# SubSchHVCotrol.net
KiCad netlist of a schematic drawn in Altium Designer
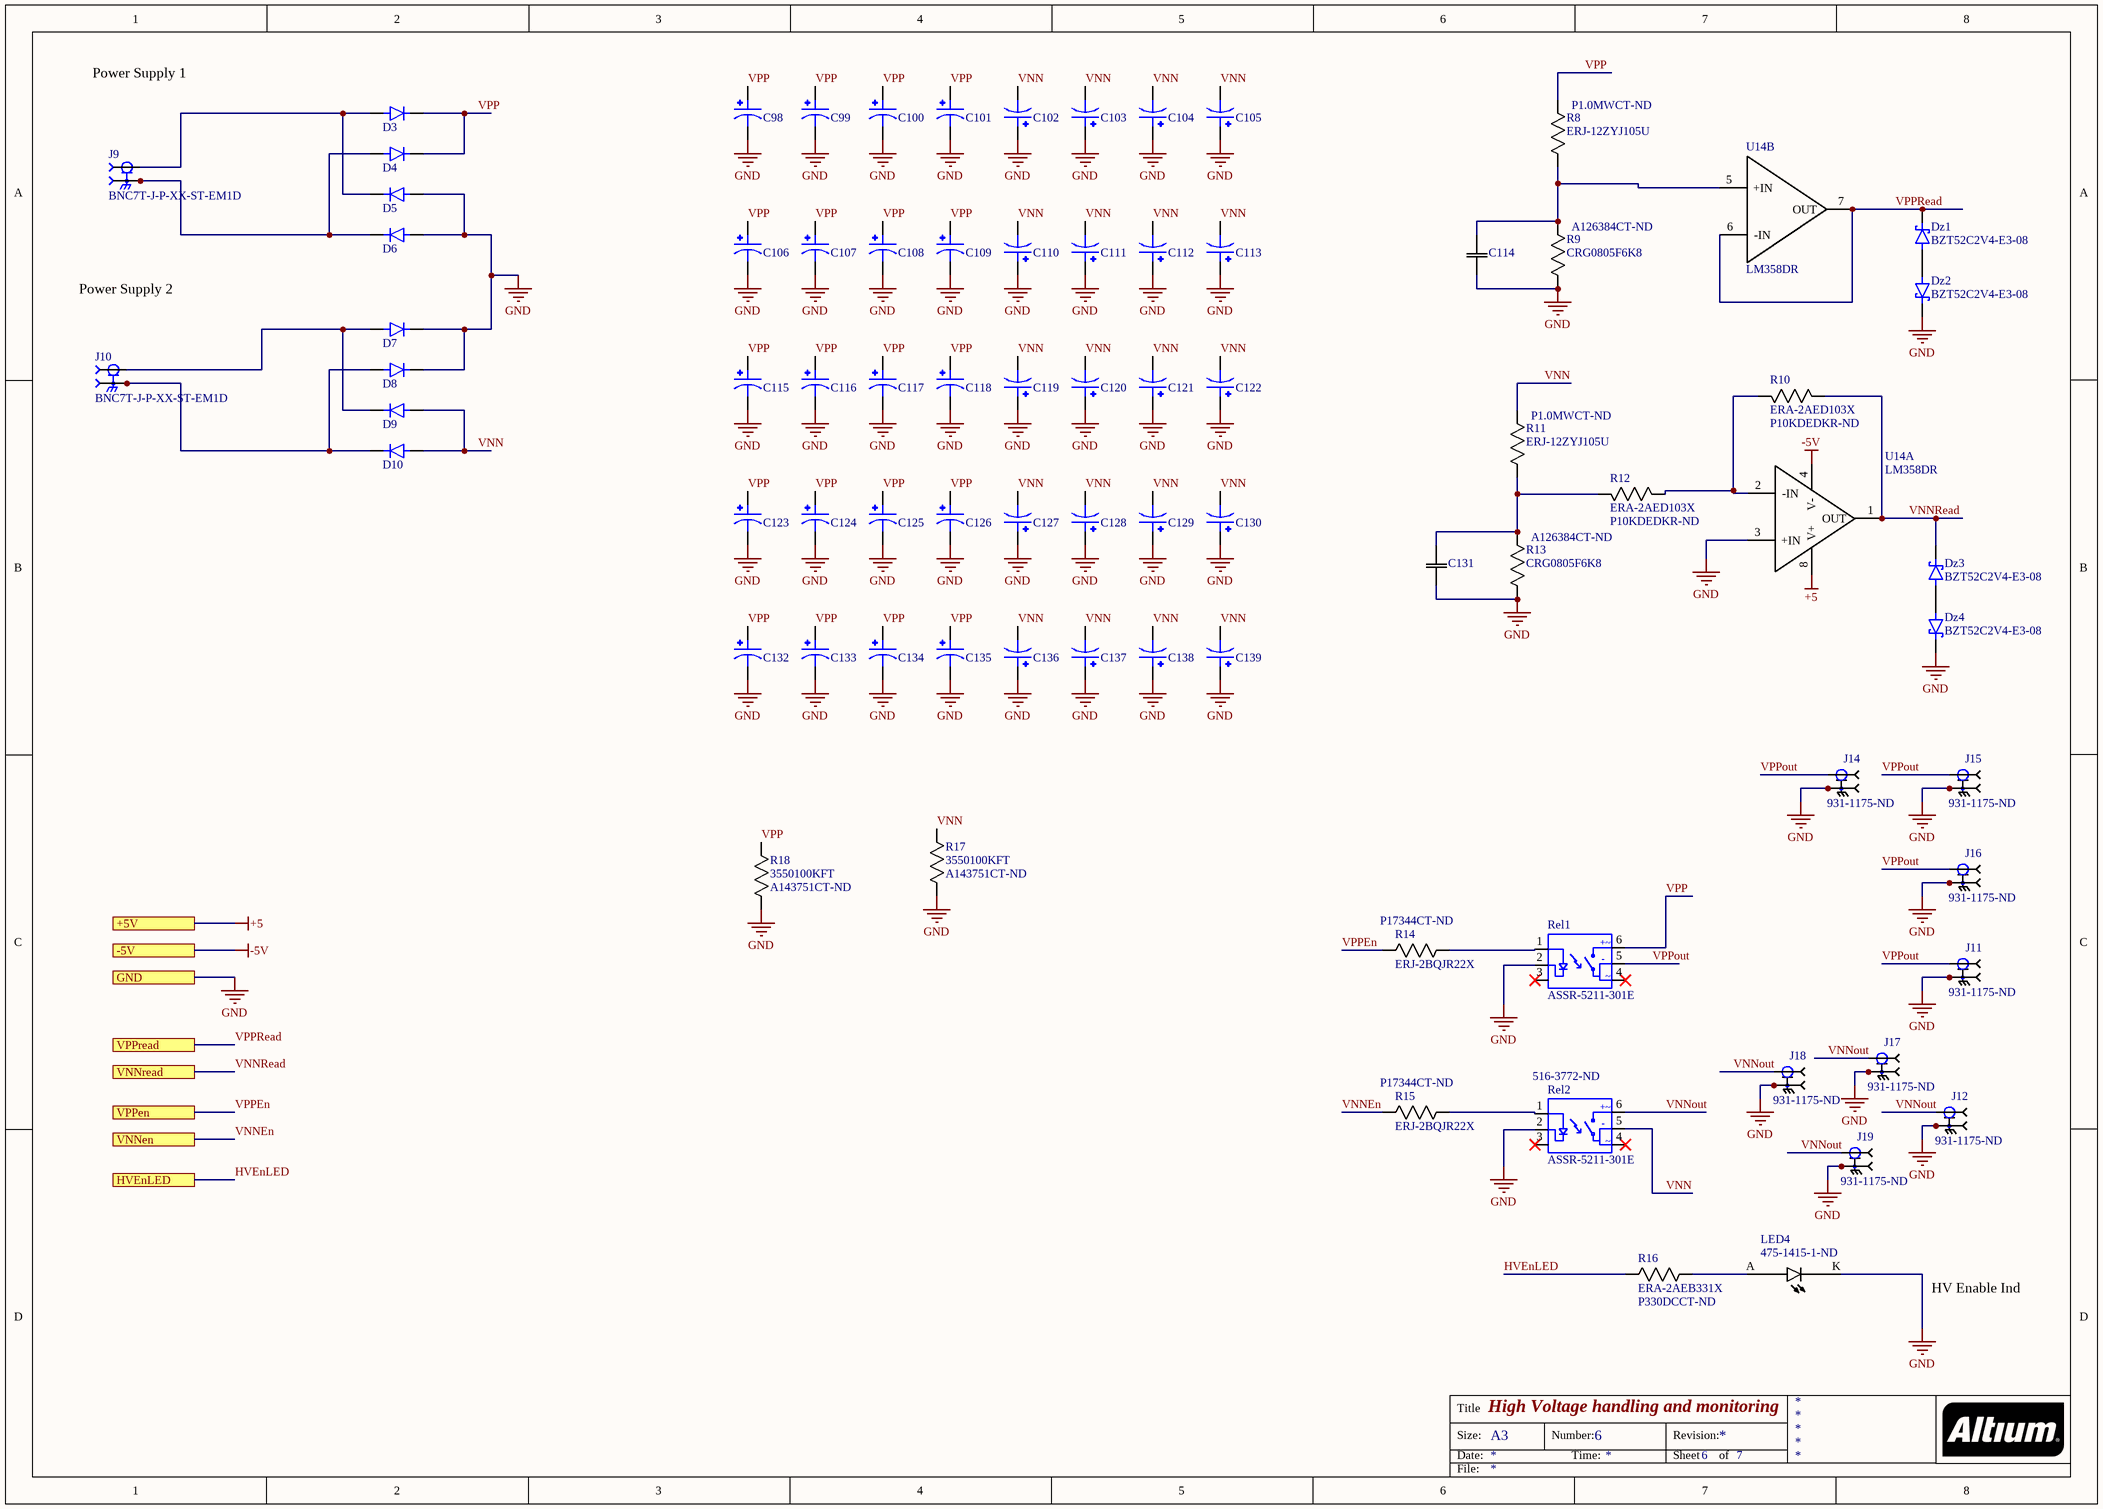
[diagram p0: SubSchHVCotrol.SchDoc]

(export (version "E")
  (design (tool "Eeschema 10.0.6"))
  (components
    (comp (ref "C98")
      (value "EDH336M400A9TAA")
      (footprint "CAPAE1700X1700N")
      (description "33ÂµF 400V Aluminum Electrolytic Capacitors Radial, Can - SMD 2000 Hrs @ 105Â°C")
      (fields (field (name "MF") "KEMET"))
      (libsource (lib "") (part "EDH336M400A9TAA_1"))
    )
    (comp (ref "C99")
      (value "EDH336M400A9TAA")
      (footprint "CAPAE1700X1700N")
      (description "33ÂµF 400V Aluminum Electrolytic Capacitors Radial, Can - SMD 2000 Hrs @ 105Â°C")
      (fields (field (name "MF") "KEMET"))
      (libsource (lib "") (part "EDH336M400A9TAA_1"))
    )
    (comp (ref "C100")
      (value "EDH336M400A9TAA")
      (footprint "CAPAE1700X1700N")
      (description "33ÂµF 400V Aluminum Electrolytic Capacitors Radial, Can - SMD 2000 Hrs @ 105Â°C")
      (fields (field (name "MF") "KEMET"))
      (libsource (lib "") (part "EDH336M400A9TAA_1"))
    )
    (comp (ref "C101")
      (value "EDH336M400A9TAA")
      (footprint "CAPAE1700X1700N")
      (description "33ÂµF 400V Aluminum Electrolytic Capacitors Radial, Can - SMD 2000 Hrs @ 105Â°C")
      (fields (field (name "MF") "KEMET"))
      (libsource (lib "") (part "EDH336M400A9TAA_1"))
    )
    (comp (ref "C102")
      (value "EDH336M400A9TAA")
      (footprint "CAPAE1700X1700N")
      (description "33ÂµF 400V Aluminum Electrolytic Capacitors Radial, Can - SMD 2000 Hrs @ 105Â°C")
      (fields (field (name "MF") "KEMET"))
      (libsource (lib "Afshin Library") (part "EDH336M400A9TAA"))
    )
    (comp (ref "C103")
      (value "EDH336M400A9TAA")
      (footprint "CAPAE1700X1700N")
      (description "33ÂµF 400V Aluminum Electrolytic Capacitors Radial, Can - SMD 2000 Hrs @ 105Â°C")
      (fields (field (name "MF") "KEMET"))
      (libsource (lib "Afshin Library") (part "EDH336M400A9TAA"))
    )
    (comp (ref "C104")
      (value "EDH336M400A9TAA")
      (footprint "CAPAE1700X1700N")
      (description "33ÂµF 400V Aluminum Electrolytic Capacitors Radial, Can - SMD 2000 Hrs @ 105Â°C")
      (fields (field (name "MF") "KEMET"))
      (libsource (lib "Afshin Library") (part "EDH336M400A9TAA"))
    )
    (comp (ref "C105")
      (value "EDH336M400A9TAA")
      (footprint "CAPAE1700X1700N")
      (description "33ÂµF 400V Aluminum Electrolytic Capacitors Radial, Can - SMD 2000 Hrs @ 105Â°C")
      (fields (field (name "MF") "KEMET"))
      (libsource (lib "Afshin Library") (part "EDH336M400A9TAA"))
    )
    (comp (ref "C106")
      (value "EDH336M400A9TAA")
      (footprint "CAPAE1700X1700N")
      (description "33ÂµF 400V Aluminum Electrolytic Capacitors Radial, Can - SMD 2000 Hrs @ 105Â°C")
      (fields (field (name "MF") "KEMET"))
      (libsource (lib "") (part "EDH336M400A9TAA_1"))
    )
    (comp (ref "C107")
      (value "EDH336M400A9TAA")
      (footprint "CAPAE1700X1700N")
      (description "33ÂµF 400V Aluminum Electrolytic Capacitors Radial, Can - SMD 2000 Hrs @ 105Â°C")
      (fields (field (name "MF") "KEMET"))
      (libsource (lib "") (part "EDH336M400A9TAA_1"))
    )
    (comp (ref "C108")
      (value "EDH336M400A9TAA")
      (footprint "CAPAE1700X1700N")
      (description "33ÂµF 400V Aluminum Electrolytic Capacitors Radial, Can - SMD 2000 Hrs @ 105Â°C")
      (fields (field (name "MF") "KEMET"))
      (libsource (lib "") (part "EDH336M400A9TAA_1"))
    )
    (comp (ref "C109")
      (value "EDH336M400A9TAA")
      (footprint "CAPAE1700X1700N")
      (description "33ÂµF 400V Aluminum Electrolytic Capacitors Radial, Can - SMD 2000 Hrs @ 105Â°C")
      (fields (field (name "MF") "KEMET"))
      (libsource (lib "") (part "EDH336M400A9TAA_1"))
    )
    (comp (ref "C110")
      (value "EDH336M400A9TAA")
      (footprint "CAPAE1700X1700N")
      (description "33ÂµF 400V Aluminum Electrolytic Capacitors Radial, Can - SMD 2000 Hrs @ 105Â°C")
      (fields (field (name "MF") "KEMET"))
      (libsource (lib "Afshin Library") (part "EDH336M400A9TAA"))
    )
    (comp (ref "C111")
      (value "EDH336M400A9TAA")
      (footprint "CAPAE1700X1700N")
      (description "33ÂµF 400V Aluminum Electrolytic Capacitors Radial, Can - SMD 2000 Hrs @ 105Â°C")
      (fields (field (name "MF") "KEMET"))
      (libsource (lib "Afshin Library") (part "EDH336M400A9TAA"))
    )
    (comp (ref "C112")
      (value "EDH336M400A9TAA")
      (footprint "CAPAE1700X1700N")
      (description "33ÂµF 400V Aluminum Electrolytic Capacitors Radial, Can - SMD 2000 Hrs @ 105Â°C")
      (fields (field (name "MF") "KEMET"))
      (libsource (lib "Afshin Library") (part "EDH336M400A9TAA"))
    )
    (comp (ref "C113")
      (value "EDH336M400A9TAA")
      (footprint "CAPAE1700X1700N")
      (description "33ÂµF 400V Aluminum Electrolytic Capacitors Radial, Can - SMD 2000 Hrs @ 105Â°C")
      (fields (field (name "MF") "KEMET"))
      (libsource (lib "Afshin Library") (part "EDH336M400A9TAA"))
    )
    (comp (ref "C114")
      (value "C0805C104Z5VACTU")
      (footprint "C0805")
      (libsource (lib "Afshin Library") (part "Cap_0805"))
    )
    (comp (ref "C115")
      (value "EDH336M400A9TAA")
      (footprint "CAPAE1700X1700N")
      (description "33ÂµF 400V Aluminum Electrolytic Capacitors Radial, Can - SMD 2000 Hrs @ 105Â°C")
      (fields (field (name "MF") "KEMET"))
      (libsource (lib "") (part "EDH336M400A9TAA_1"))
    )
    (comp (ref "C116")
      (value "EDH336M400A9TAA")
      (footprint "CAPAE1700X1700N")
      (description "33ÂµF 400V Aluminum Electrolytic Capacitors Radial, Can - SMD 2000 Hrs @ 105Â°C")
      (fields (field (name "MF") "KEMET"))
      (libsource (lib "") (part "EDH336M400A9TAA_1"))
    )
    (comp (ref "C117")
      (value "EDH336M400A9TAA")
      (footprint "CAPAE1700X1700N")
      (description "33ÂµF 400V Aluminum Electrolytic Capacitors Radial, Can - SMD 2000 Hrs @ 105Â°C")
      (fields (field (name "MF") "KEMET"))
      (libsource (lib "") (part "EDH336M400A9TAA_1"))
    )
    (comp (ref "C118")
      (value "EDH336M400A9TAA")
      (footprint "CAPAE1700X1700N")
      (description "33ÂµF 400V Aluminum Electrolytic Capacitors Radial, Can - SMD 2000 Hrs @ 105Â°C")
      (fields (field (name "MF") "KEMET"))
      (libsource (lib "") (part "EDH336M400A9TAA_1"))
    )
    (comp (ref "C119")
      (value "EDH336M400A9TAA")
      (footprint "CAPAE1700X1700N")
      (description "33ÂµF 400V Aluminum Electrolytic Capacitors Radial, Can - SMD 2000 Hrs @ 105Â°C")
      (fields (field (name "MF") "KEMET"))
      (libsource (lib "Afshin Library") (part "EDH336M400A9TAA"))
    )
    (comp (ref "C120")
      (value "EDH336M400A9TAA")
      (footprint "CAPAE1700X1700N")
      (description "33ÂµF 400V Aluminum Electrolytic Capacitors Radial, Can - SMD 2000 Hrs @ 105Â°C")
      (fields (field (name "MF") "KEMET"))
      (libsource (lib "Afshin Library") (part "EDH336M400A9TAA"))
    )
    (comp (ref "C121")
      (value "EDH336M400A9TAA")
      (footprint "CAPAE1700X1700N")
      (description "33ÂµF 400V Aluminum Electrolytic Capacitors Radial, Can - SMD 2000 Hrs @ 105Â°C")
      (fields (field (name "MF") "KEMET"))
      (libsource (lib "Afshin Library") (part "EDH336M400A9TAA"))
    )
    (comp (ref "C122")
      (value "EDH336M400A9TAA")
      (footprint "CAPAE1700X1700N")
      (description "33ÂµF 400V Aluminum Electrolytic Capacitors Radial, Can - SMD 2000 Hrs @ 105Â°C")
      (fields (field (name "MF") "KEMET"))
      (libsource (lib "Afshin Library") (part "EDH336M400A9TAA"))
    )
    (comp (ref "C123")
      (value "EDH336M400A9TAA")
      (footprint "CAPAE1700X1700N")
      (description "33ÂµF 400V Aluminum Electrolytic Capacitors Radial, Can - SMD 2000 Hrs @ 105Â°C")
      (fields (field (name "MF") "KEMET"))
      (libsource (lib "") (part "EDH336M400A9TAA_1"))
    )
    (comp (ref "C124")
      (value "EDH336M400A9TAA")
      (footprint "CAPAE1700X1700N")
      (description "33ÂµF 400V Aluminum Electrolytic Capacitors Radial, Can - SMD 2000 Hrs @ 105Â°C")
      (fields (field (name "MF") "KEMET"))
      (libsource (lib "") (part "EDH336M400A9TAA_1"))
    )
    (comp (ref "C125")
      (value "EDH336M400A9TAA")
      (footprint "CAPAE1700X1700N")
      (description "33ÂµF 400V Aluminum Electrolytic Capacitors Radial, Can - SMD 2000 Hrs @ 105Â°C")
      (fields (field (name "MF") "KEMET"))
      (libsource (lib "") (part "EDH336M400A9TAA_1"))
    )
    (comp (ref "C126")
      (value "EDH336M400A9TAA")
      (footprint "CAPAE1700X1700N")
      (description "33ÂµF 400V Aluminum Electrolytic Capacitors Radial, Can - SMD 2000 Hrs @ 105Â°C")
      (fields (field (name "MF") "KEMET"))
      (libsource (lib "") (part "EDH336M400A9TAA_1"))
    )
    (comp (ref "C127")
      (value "EDH336M400A9TAA")
      (footprint "CAPAE1700X1700N")
      (description "33ÂµF 400V Aluminum Electrolytic Capacitors Radial, Can - SMD 2000 Hrs @ 105Â°C")
      (fields (field (name "MF") "KEMET"))
      (libsource (lib "Afshin Library") (part "EDH336M400A9TAA"))
    )
    (comp (ref "C128")
      (value "EDH336M400A9TAA")
      (footprint "CAPAE1700X1700N")
      (description "33ÂµF 400V Aluminum Electrolytic Capacitors Radial, Can - SMD 2000 Hrs @ 105Â°C")
      (fields (field (name "MF") "KEMET"))
      (libsource (lib "Afshin Library") (part "EDH336M400A9TAA"))
    )
    (comp (ref "C129")
      (value "EDH336M400A9TAA")
      (footprint "CAPAE1700X1700N")
      (description "33ÂµF 400V Aluminum Electrolytic Capacitors Radial, Can - SMD 2000 Hrs @ 105Â°C")
      (fields (field (name "MF") "KEMET"))
      (libsource (lib "Afshin Library") (part "EDH336M400A9TAA"))
    )
    (comp (ref "C130")
      (value "EDH336M400A9TAA")
      (footprint "CAPAE1700X1700N")
      (description "33ÂµF 400V Aluminum Electrolytic Capacitors Radial, Can - SMD 2000 Hrs @ 105Â°C")
      (fields (field (name "MF") "KEMET"))
      (libsource (lib "Afshin Library") (part "EDH336M400A9TAA"))
    )
    (comp (ref "C131")
      (value "C0805C104Z5VACTU")
      (footprint "C0805")
      (libsource (lib "Afshin Library") (part "Cap_0805"))
    )
    (comp (ref "C132")
      (value "EDH336M400A9TAA")
      (footprint "CAPAE1700X1700N")
      (description "33ÂµF 400V Aluminum Electrolytic Capacitors Radial, Can - SMD 2000 Hrs @ 105Â°C")
      (fields (field (name "MF") "KEMET"))
      (libsource (lib "") (part "EDH336M400A9TAA_1"))
    )
    (comp (ref "C133")
      (value "EDH336M400A9TAA")
      (footprint "CAPAE1700X1700N")
      (description "33ÂµF 400V Aluminum Electrolytic Capacitors Radial, Can - SMD 2000 Hrs @ 105Â°C")
      (fields (field (name "MF") "KEMET"))
      (libsource (lib "") (part "EDH336M400A9TAA_1"))
    )
    (comp (ref "C134")
      (value "EDH336M400A9TAA")
      (footprint "CAPAE1700X1700N")
      (description "33ÂµF 400V Aluminum Electrolytic Capacitors Radial, Can - SMD 2000 Hrs @ 105Â°C")
      (fields (field (name "MF") "KEMET"))
      (libsource (lib "") (part "EDH336M400A9TAA_1"))
    )
    (comp (ref "C135")
      (value "EDH336M400A9TAA")
      (footprint "CAPAE1700X1700N")
      (description "33ÂµF 400V Aluminum Electrolytic Capacitors Radial, Can - SMD 2000 Hrs @ 105Â°C")
      (fields (field (name "MF") "KEMET"))
      (libsource (lib "") (part "EDH336M400A9TAA_1"))
    )
    (comp (ref "C136")
      (value "EDH336M400A9TAA")
      (footprint "CAPAE1700X1700N")
      (description "33ÂµF 400V Aluminum Electrolytic Capacitors Radial, Can - SMD 2000 Hrs @ 105Â°C")
      (fields (field (name "MF") "KEMET"))
      (libsource (lib "Afshin Library") (part "EDH336M400A9TAA"))
    )
    (comp (ref "C137")
      (value "EDH336M400A9TAA")
      (footprint "CAPAE1700X1700N")
      (description "33ÂµF 400V Aluminum Electrolytic Capacitors Radial, Can - SMD 2000 Hrs @ 105Â°C")
      (fields (field (name "MF") "KEMET"))
      (libsource (lib "Afshin Library") (part "EDH336M400A9TAA"))
    )
    (comp (ref "C138")
      (value "EDH336M400A9TAA")
      (footprint "CAPAE1700X1700N")
      (description "33ÂµF 400V Aluminum Electrolytic Capacitors Radial, Can - SMD 2000 Hrs @ 105Â°C")
      (fields (field (name "MF") "KEMET"))
      (libsource (lib "Afshin Library") (part "EDH336M400A9TAA"))
    )
    (comp (ref "C139")
      (value "EDH336M400A9TAA")
      (footprint "CAPAE1700X1700N")
      (description "33ÂµF 400V Aluminum Electrolytic Capacitors Radial, Can - SMD 2000 Hrs @ 105Â°C")
      (fields (field (name "MF") "KEMET"))
      (libsource (lib "Afshin Library") (part "EDH336M400A9TAA"))
    )
    (comp (ref "D3")
      (value "CD1408-R11000")
      (footprint "CD1408")
      (description "Diode Standard 1000V 1A Surface Mount 1408")
      (libsource (lib "Afshin Library") (part "CD1408-R11000"))
    )
    (comp (ref "D4")
      (value "CD1408-R11000")
      (footprint "CD1408")
      (description "Diode Standard 1000V 1A Surface Mount 1408")
      (libsource (lib "Afshin Library") (part "CD1408-R11000"))
    )
    (comp (ref "D5")
      (value "CD1408-R11000")
      (footprint "CD1408")
      (description "Diode Standard 1000V 1A Surface Mount 1408")
      (libsource (lib "Afshin Library") (part "CD1408-R11000"))
    )
    (comp (ref "D6")
      (value "CD1408-R11000")
      (footprint "CD1408")
      (description "Diode Standard 1000V 1A Surface Mount 1408")
      (libsource (lib "Afshin Library") (part "CD1408-R11000"))
    )
    (comp (ref "D7")
      (value "CD1408-R11000")
      (footprint "CD1408")
      (description "Diode Standard 1000V 1A Surface Mount 1408")
      (libsource (lib "Afshin Library") (part "CD1408-R11000"))
    )
    (comp (ref "D8")
      (value "CD1408-R11000")
      (footprint "CD1408")
      (description "Diode Standard 1000V 1A Surface Mount 1408")
      (libsource (lib "Afshin Library") (part "CD1408-R11000"))
    )
    (comp (ref "D9")
      (value "CD1408-R11000")
      (footprint "CD1408")
      (description "Diode Standard 1000V 1A Surface Mount 1408")
      (libsource (lib "Afshin Library") (part "CD1408-R11000"))
    )
    (comp (ref "D10")
      (value "CD1408-R11000")
      (footprint "CD1408")
      (description "Diode Standard 1000V 1A Surface Mount 1408")
      (libsource (lib "Afshin Library") (part "CD1408-R11000"))
    )
    (comp (ref "Dz1")
      (value "BZT52C2V4-E3-08")
      (footprint "SOD-123")
      (description "Zener Diode 2.4V 410mW ±5% Surface Mount SOD-123")
      (libsource (lib "Afshin Library") (part "BZT52C2V4-E3-08"))
    )
    (comp (ref "Dz2")
      (value "BZT52C2V4-E3-08")
      (footprint "SOD-123")
      (description "Zener Diode 2.4V 410mW ±5% Surface Mount SOD-123")
      (libsource (lib "Afshin Library") (part "BZT52C2V4-E3-08"))
    )
    (comp (ref "Dz3")
      (value "BZT52C2V4-E3-08")
      (footprint "SOD-123")
      (description "Zener Diode 2.4V 410mW ±5% Surface Mount SOD-123")
      (libsource (lib "Afshin Library") (part "BZT52C2V4-E3-08"))
    )
    (comp (ref "Dz4")
      (value "BZT52C2V4-E3-08")
      (footprint "SOD-123")
      (description "Zener Diode 2.4V 410mW ±5% Surface Mount SOD-123")
      (libsource (lib "Afshin Library") (part "BZT52C2V4-E3-08"))
    )
    (comp (ref "J9")
      (value "BNC7T-J-P-XX-ST-EM1D")
      (footprint "SAMTEC_BNC7T-J-P-XX-ST-EM1D")
      (description "BNC Connector Jack, Female Socket 75Ohm Board Edge, End Launch; Panel Mount Solder")
      (fields (field (name "MP") "BNC7T-J-P-GN-ST-EM1D") (field (name "MF") "Samtec Inc."))
      (libsource (lib "Afshin Library") (part "BNC7T-J-P-XX-ST-EM1D"))
    )
    (comp (ref "J10")
      (value "BNC7T-J-P-XX-ST-EM1D")
      (footprint "SAMTEC_BNC7T-J-P-XX-ST-EM1D")
      (description "BNC Connector Jack, Female Socket 75Ohm Board Edge, End Launch; Panel Mount Solder")
      (fields (field (name "MP") "BNC7T-J-P-GN-ST-EM1D") (field (name "MF") "Samtec Inc."))
      (libsource (lib "Afshin Library") (part "BNC7T-J-P-XX-ST-EM1D"))
    )
    (comp (ref "J11")
      (value "EMPCB.SMAFSTJ.B.HT")
      (footprint "*TAOGLAS_EMPCB.SMAFSTJ.B.HT_EMPCB.SMAFSTJ.B.HT(Primary)")
      (description "SMA Connector Jack, Female Socket 50Ohm Board Edge, End Launch Solder")
      (fields
        (field (name "MF") "Taoglas Limited")
        (field (name "DIGI-KEY_PART_NUMBER") "931-1175-ND")
        (field (name "SUPPLIER PART NUMBER 1") "931-1175-ND")
      )
      (libsource (lib "Afshin Library") (part "EMPCB.SMAFSTJ.B.HT"))
    )
    (comp (ref "J12")
      (value "EMPCB.SMAFSTJ.B.HT")
      (footprint "*TAOGLAS_EMPCB.SMAFSTJ.B.HT_EMPCB.SMAFSTJ.B.HT(Primary)")
      (description "SMA Connector Jack, Female Socket 50Ohm Board Edge, End Launch Solder")
      (fields
        (field (name "MF") "Taoglas Limited")
        (field (name "DIGI-KEY_PART_NUMBER") "931-1175-ND")
        (field (name "SUPPLIER PART NUMBER 1") "931-1175-ND")
      )
      (libsource (lib "Afshin Library") (part "EMPCB.SMAFSTJ.B.HT"))
    )
    (comp (ref "J14")
      (value "EMPCB.SMAFSTJ.B.HT")
      (footprint "*TAOGLAS_EMPCB.SMAFSTJ.B.HT_EMPCB.SMAFSTJ.B.HT(Primary)")
      (description "SMA Connector Jack, Female Socket 50Ohm Board Edge, End Launch Solder")
      (fields
        (field (name "MF") "Taoglas Limited")
        (field (name "DIGI-KEY_PART_NUMBER") "931-1175-ND")
        (field (name "SUPPLIER PART NUMBER 1") "931-1175-ND")
      )
      (libsource (lib "Afshin Library") (part "EMPCB.SMAFSTJ.B.HT"))
    )
    (comp (ref "J15")
      (value "EMPCB.SMAFSTJ.B.HT")
      (footprint "*TAOGLAS_EMPCB.SMAFSTJ.B.HT_EMPCB.SMAFSTJ.B.HT(Primary)")
      (description "SMA Connector Jack, Female Socket 50Ohm Board Edge, End Launch Solder")
      (fields
        (field (name "MF") "Taoglas Limited")
        (field (name "DIGI-KEY_PART_NUMBER") "931-1175-ND")
        (field (name "SUPPLIER PART NUMBER 1") "931-1175-ND")
      )
      (libsource (lib "Afshin Library") (part "EMPCB.SMAFSTJ.B.HT"))
    )
    (comp (ref "J16")
      (value "EMPCB.SMAFSTJ.B.HT")
      (footprint "*TAOGLAS_EMPCB.SMAFSTJ.B.HT_EMPCB.SMAFSTJ.B.HT(Primary)")
      (description "SMA Connector Jack, Female Socket 50Ohm Board Edge, End Launch Solder")
      (fields
        (field (name "MF") "Taoglas Limited")
        (field (name "DIGI-KEY_PART_NUMBER") "931-1175-ND")
        (field (name "SUPPLIER PART NUMBER 1") "931-1175-ND")
      )
      (libsource (lib "Afshin Library") (part "EMPCB.SMAFSTJ.B.HT"))
    )
    (comp (ref "J17")
      (value "EMPCB.SMAFSTJ.B.HT")
      (footprint "*TAOGLAS_EMPCB.SMAFSTJ.B.HT_EMPCB.SMAFSTJ.B.HT(Primary)")
      (description "SMA Connector Jack, Female Socket 50Ohm Board Edge, End Launch Solder")
      (fields
        (field (name "MF") "Taoglas Limited")
        (field (name "DIGI-KEY_PART_NUMBER") "931-1175-ND")
        (field (name "SUPPLIER PART NUMBER 1") "931-1175-ND")
      )
      (libsource (lib "Afshin Library") (part "EMPCB.SMAFSTJ.B.HT"))
    )
    (comp (ref "J18")
      (value "EMPCB.SMAFSTJ.B.HT")
      (footprint "*TAOGLAS_EMPCB.SMAFSTJ.B.HT_EMPCB.SMAFSTJ.B.HT(Primary)")
      (description "SMA Connector Jack, Female Socket 50Ohm Board Edge, End Launch Solder")
      (fields
        (field (name "MF") "Taoglas Limited")
        (field (name "DIGI-KEY_PART_NUMBER") "931-1175-ND")
        (field (name "SUPPLIER PART NUMBER 1") "931-1175-ND")
      )
      (libsource (lib "Afshin Library") (part "EMPCB.SMAFSTJ.B.HT"))
    )
    (comp (ref "J19")
      (value "EMPCB.SMAFSTJ.B.HT")
      (footprint "*TAOGLAS_EMPCB.SMAFSTJ.B.HT_EMPCB.SMAFSTJ.B.HT(Primary)")
      (description "SMA Connector Jack, Female Socket 50Ohm Board Edge, End Launch Solder")
      (fields
        (field (name "MF") "Taoglas Limited")
        (field (name "DIGI-KEY_PART_NUMBER") "931-1175-ND")
        (field (name "SUPPLIER PART NUMBER 1") "931-1175-ND")
      )
      (libsource (lib "Afshin Library") (part "EMPCB.SMAFSTJ.B.HT"))
    )
    (comp (ref "LED4")
      (value "LH R974-LP-1")
      (footprint "LEDr0805")
      (description "LED:\r\nLH R974-LP-1\r\nLG R971-KN-1\r\nLY R976-PS-36")
      (fields (field (name "SUPPLIER PART NUMBER 1") "475-1415-1-ND"))
      (libsource (lib "Afshin Library") (part "LED_0805"))
    )
    (comp (ref "R8")
      (value "ERJ-12ZYJ105U")
      (footprint "R2010")
      (description "Chip Resistor 2010 (5025 Metric) Automotive AEC-Q200 Thick Film")
      (fields (field (name "SUPPLIER PART NUMBER 1") "P1.0MWCT-ND"))
      (libsource (lib "Afshin Library") (part "Res_2010"))
    )
    (comp (ref "R9")
      (value "CRG0805F6K8")
      (footprint "0805")
      (fields (field (name "SUPPLIER PART NUMBER 1") "A126384CT-ND"))
      (libsource (lib "Afshin Library") (part "Res_0805"))
    )
    (comp (ref "R10")
      (value "ERA-2AED103X")
      (footprint "R0402")
      (fields (field (name "SUPPLIER PART NUMBER 1") "P10KDEDKR-ND"))
      (libsource (lib "Afshin Library") (part "Res_0805"))
    )
    (comp (ref "R11")
      (value "ERJ-12ZYJ105U")
      (footprint "R2010")
      (description "Chip Resistor 2010 (5025 Metric) Automotive AEC-Q200 Thick Film")
      (fields (field (name "SUPPLIER PART NUMBER 1") "P1.0MWCT-ND"))
      (libsource (lib "Afshin Library") (part "Res_2010"))
    )
    (comp (ref "R12")
      (value "ERA-2AED103X")
      (footprint "R0402")
      (fields (field (name "SUPPLIER PART NUMBER 1") "P10KDEDKR-ND"))
      (libsource (lib "Afshin Library") (part "Res_0805"))
    )
    (comp (ref "R13")
      (value "CRG0805F6K8")
      (footprint "0805")
      (fields (field (name "SUPPLIER PART NUMBER 1") "A126384CT-ND"))
      (libsource (lib "Afshin Library") (part "Res_0805"))
    )
    (comp (ref "R14")
      (value "ERJ-2BQJR22X")
      (footprint "0402-A")
      (fields (field (name "SUPPLIER PART NUMBER 1") "P17344CT-ND"))
      (libsource (lib "Afshin Library") (part "Res_0805"))
    )
    (comp (ref "R15")
      (value "ERJ-2BQJR22X")
      (footprint "0402-A")
      (fields (field (name "SUPPLIER PART NUMBER 1") "P17344CT-ND"))
      (libsource (lib "Afshin Library") (part "Res_0805"))
    )
    (comp (ref "R16")
      (value "ERA-2AEB331X")
      (footprint "0402")
      (fields (field (name "SUPPLIER PART NUMBER 1") "P330DCCT-ND"))
      (libsource (lib "Afshin Library") (part "Res_0805"))
    )
    (comp (ref "R17")
      (value "3550100KFT")
      (footprint "355047KJT")
      (description "100K 5W")
      (fields (field (name "SUPPLIER PART NUMBER 1") "A143751CT-ND"))
      (libsource (lib "Afshin Library") (part "Res_3550"))
    )
    (comp (ref "R18")
      (value "3550100KFT")
      (footprint "355047KJT")
      (description "100K 5W")
      (fields (field (name "SUPPLIER PART NUMBER 1") "A143751CT-ND"))
      (libsource (lib "Afshin Library") (part "Res_3550"))
    )
    (comp (ref "Rel1")
      (value "ASSR-5211-301E")
      (footprint "6-DIPGullWing")
      (description "Solid State SPST-NO (1 Form A) 6-SMD (0.300\", 7.62mm)\r\nSSR RELAY SPST-NO 200MA 0-600V")
      (libsource (lib "Afshin Library") (part "ASSR-5211-301E"))
    )
    (comp (ref "Rel2")
      (value "ASSR-5211-301E")
      (footprint "6-DIPGullWing")
      (description "Solid State SPST-NO (1 Form A) 6-SMD (0.300\", 7.62mm)\r\nSSR RELAY SPST-NO 200MA 0-600V")
      (fields (field (name "SUPPLIER PART NUMBER 1") "516-3772-ND"))
      (libsource (lib "Afshin Library") (part "ASSR-5211-301E"))
    )
    (comp (ref "U14")
      (value "LM358DR")
      (footprint "SOIC127P600X175-8N")
      (libsource (lib "") (part "LM358DR_1"))
    )
  )
  (nets
    (net (code "1") (name "+5") (class "Default")
      (node (ref "U14") (pin "8") (pinfunction "V+_8") (pintype "power_in"))
    )
    (net (code "2") (name "-5V") (class "Default")
      (node (ref "U14") (pin "4") (pinfunction "V-_4") (pintype "power_in"))
    )
    (net (code "3") (name "/HVEnLED") (class "Default")
      (node (ref "R16") (pin "2") (pinfunction "2_2") (pintype "passive"))
    )
    (net (code "4") (name "/VNN") (class "Default")
      (node (ref "C102") (pin "2") (pinfunction "NEG_2") (pintype "passive"))
      (node (ref "C103") (pin "2") (pinfunction "NEG_2") (pintype "passive"))
      (node (ref "C104") (pin "2") (pinfunction "NEG_2") (pintype "passive"))
      (node (ref "C105") (pin "2") (pinfunction "NEG_2") (pintype "passive"))
      (node (ref "C110") (pin "2") (pinfunction "NEG_2") (pintype "passive"))
      (node (ref "C111") (pin "2") (pinfunction "NEG_2") (pintype "passive"))
      (node (ref "C112") (pin "2") (pinfunction "NEG_2") (pintype "passive"))
      (node (ref "C113") (pin "2") (pinfunction "NEG_2") (pintype "passive"))
      (node (ref "C119") (pin "2") (pinfunction "NEG_2") (pintype "passive"))
      (node (ref "C120") (pin "2") (pinfunction "NEG_2") (pintype "passive"))
      (node (ref "C121") (pin "2") (pinfunction "NEG_2") (pintype "passive"))
      (node (ref "C122") (pin "2") (pinfunction "NEG_2") (pintype "passive"))
      (node (ref "C127") (pin "2") (pinfunction "NEG_2") (pintype "passive"))
      (node (ref "C128") (pin "2") (pinfunction "NEG_2") (pintype "passive"))
      (node (ref "C129") (pin "2") (pinfunction "NEG_2") (pintype "passive"))
      (node (ref "C130") (pin "2") (pinfunction "NEG_2") (pintype "passive"))
      (node (ref "C136") (pin "2") (pinfunction "NEG_2") (pintype "passive"))
      (node (ref "C137") (pin "2") (pinfunction "NEG_2") (pintype "passive"))
      (node (ref "C138") (pin "2") (pinfunction "NEG_2") (pintype "passive"))
      (node (ref "C139") (pin "2") (pinfunction "NEG_2") (pintype "passive"))
      (node (ref "D10") (pin "2") (pinfunction "2_2") (pintype "passive"))
      (node (ref "D9") (pin "2") (pinfunction "2_2") (pintype "passive"))
      (node (ref "R11") (pin "2") (pinfunction "2_2") (pintype "passive"))
      (node (ref "R17") (pin "2") (pinfunction "2_2") (pintype "passive"))
      (node (ref "Rel2") (pin "5") (pinfunction "5_5") (pintype "passive"))
    )
    (net (code "5") (name "/VNNEn") (class "Default")
      (node (ref "R15") (pin "2") (pinfunction "2_2") (pintype "passive"))
    )
    (net (code "6") (name "/VNNRead") (class "Default")
      (node (ref "Dz3") (pin "1") (pinfunction "K_1") (pintype "passive"))
      (node (ref "R10") (pin "2") (pinfunction "2_2") (pintype "passive"))
      (node (ref "U14") (pin "1") (pinfunction "OUT_1") (pintype "passive"))
    )
    (net (code "7") (name "/VNNout") (class "Default")
      (node (ref "J12") (pin "1") (pinfunction "1_1") (pintype "passive"))
      (node (ref "J17") (pin "1") (pinfunction "1_1") (pintype "passive"))
      (node (ref "J18") (pin "1") (pinfunction "1_1") (pintype "passive"))
      (node (ref "J19") (pin "1") (pinfunction "1_1") (pintype "passive"))
      (node (ref "Rel2") (pin "6") (pinfunction "6_6") (pintype "passive"))
    )
    (net (code "8") (name "/VPP") (class "Default")
      (node (ref "C100") (pin "1") (pinfunction "POS_1") (pintype "passive"))
      (node (ref "C101") (pin "1") (pinfunction "POS_1") (pintype "passive"))
      (node (ref "C106") (pin "1") (pinfunction "POS_1") (pintype "passive"))
      (node (ref "C107") (pin "1") (pinfunction "POS_1") (pintype "passive"))
      (node (ref "C108") (pin "1") (pinfunction "POS_1") (pintype "passive"))
      (node (ref "C109") (pin "1") (pinfunction "POS_1") (pintype "passive"))
      (node (ref "C115") (pin "1") (pinfunction "POS_1") (pintype "passive"))
      (node (ref "C116") (pin "1") (pinfunction "POS_1") (pintype "passive"))
      (node (ref "C117") (pin "1") (pinfunction "POS_1") (pintype "passive"))
      (node (ref "C118") (pin "1") (pinfunction "POS_1") (pintype "passive"))
      (node (ref "C123") (pin "1") (pinfunction "POS_1") (pintype "passive"))
      (node (ref "C124") (pin "1") (pinfunction "POS_1") (pintype "passive"))
      (node (ref "C125") (pin "1") (pinfunction "POS_1") (pintype "passive"))
      (node (ref "C126") (pin "1") (pinfunction "POS_1") (pintype "passive"))
      (node (ref "C132") (pin "1") (pinfunction "POS_1") (pintype "passive"))
      (node (ref "C133") (pin "1") (pinfunction "POS_1") (pintype "passive"))
      (node (ref "C134") (pin "1") (pinfunction "POS_1") (pintype "passive"))
      (node (ref "C135") (pin "1") (pinfunction "POS_1") (pintype "passive"))
      (node (ref "C98") (pin "1") (pinfunction "POS_1") (pintype "passive"))
      (node (ref "C99") (pin "1") (pinfunction "POS_1") (pintype "passive"))
      (node (ref "D3") (pin "1") (pinfunction "1_1") (pintype "passive"))
      (node (ref "D4") (pin "1") (pinfunction "1_1") (pintype "passive"))
      (node (ref "R18") (pin "2") (pinfunction "2_2") (pintype "passive"))
      (node (ref "R8") (pin "2") (pinfunction "2_2") (pintype "passive"))
      (node (ref "Rel1") (pin "6") (pinfunction "6_6") (pintype "passive"))
    )
    (net (code "9") (name "/VPPEn") (class "Default")
      (node (ref "R14") (pin "2") (pinfunction "2_2") (pintype "passive"))
    )
    (net (code "10") (name "/VPPRead") (class "Default")
      (node (ref "Dz1") (pin "1") (pinfunction "K_1") (pintype "passive"))
      (node (ref "U14") (pin "6") (pinfunction "-IN_6") (pintype "passive"))
      (node (ref "U14") (pin "7") (pinfunction "OUT_7") (pintype "passive"))
    )
    (net (code "11") (name "/VPPout") (class "Default")
      (node (ref "J11") (pin "1") (pinfunction "1_1") (pintype "passive"))
      (node (ref "J14") (pin "1") (pinfunction "1_1") (pintype "passive"))
      (node (ref "J15") (pin "1") (pinfunction "1_1") (pintype "passive"))
      (node (ref "J16") (pin "1") (pinfunction "1_1") (pintype "passive"))
      (node (ref "Rel1") (pin "5") (pinfunction "5_5") (pintype "passive"))
    )
    (net (code "12") (name "GND") (class "Default")
      (node (ref "C100") (pin "2") (pinfunction "NEG_2") (pintype "passive"))
      (node (ref "C101") (pin "2") (pinfunction "NEG_2") (pintype "passive"))
      (node (ref "C102") (pin "1") (pinfunction "POS_1") (pintype "passive"))
      (node (ref "C103") (pin "1") (pinfunction "POS_1") (pintype "passive"))
      (node (ref "C104") (pin "1") (pinfunction "POS_1") (pintype "passive"))
      (node (ref "C105") (pin "1") (pinfunction "POS_1") (pintype "passive"))
      (node (ref "C106") (pin "2") (pinfunction "NEG_2") (pintype "passive"))
      (node (ref "C107") (pin "2") (pinfunction "NEG_2") (pintype "passive"))
      (node (ref "C108") (pin "2") (pinfunction "NEG_2") (pintype "passive"))
      (node (ref "C109") (pin "2") (pinfunction "NEG_2") (pintype "passive"))
      (node (ref "C110") (pin "1") (pinfunction "POS_1") (pintype "passive"))
      (node (ref "C111") (pin "1") (pinfunction "POS_1") (pintype "passive"))
      (node (ref "C112") (pin "1") (pinfunction "POS_1") (pintype "passive"))
      (node (ref "C113") (pin "1") (pinfunction "POS_1") (pintype "passive"))
      (node (ref "C114") (pin "1") (pinfunction "1_1") (pintype "passive"))
      (node (ref "C115") (pin "2") (pinfunction "NEG_2") (pintype "passive"))
      (node (ref "C116") (pin "2") (pinfunction "NEG_2") (pintype "passive"))
      (node (ref "C117") (pin "2") (pinfunction "NEG_2") (pintype "passive"))
      (node (ref "C118") (pin "2") (pinfunction "NEG_2") (pintype "passive"))
      (node (ref "C119") (pin "1") (pinfunction "POS_1") (pintype "passive"))
      (node (ref "C120") (pin "1") (pinfunction "POS_1") (pintype "passive"))
      (node (ref "C121") (pin "1") (pinfunction "POS_1") (pintype "passive"))
      (node (ref "C122") (pin "1") (pinfunction "POS_1") (pintype "passive"))
      (node (ref "C123") (pin "2") (pinfunction "NEG_2") (pintype "passive"))
      (node (ref "C124") (pin "2") (pinfunction "NEG_2") (pintype "passive"))
      (node (ref "C125") (pin "2") (pinfunction "NEG_2") (pintype "passive"))
      (node (ref "C126") (pin "2") (pinfunction "NEG_2") (pintype "passive"))
      (node (ref "C127") (pin "1") (pinfunction "POS_1") (pintype "passive"))
      (node (ref "C128") (pin "1") (pinfunction "POS_1") (pintype "passive"))
      (node (ref "C129") (pin "1") (pinfunction "POS_1") (pintype "passive"))
      (node (ref "C130") (pin "1") (pinfunction "POS_1") (pintype "passive"))
      (node (ref "C131") (pin "1") (pinfunction "1_1") (pintype "passive"))
      (node (ref "C132") (pin "2") (pinfunction "NEG_2") (pintype "passive"))
      (node (ref "C133") (pin "2") (pinfunction "NEG_2") (pintype "passive"))
      (node (ref "C134") (pin "2") (pinfunction "NEG_2") (pintype "passive"))
      (node (ref "C135") (pin "2") (pinfunction "NEG_2") (pintype "passive"))
      (node (ref "C136") (pin "1") (pinfunction "POS_1") (pintype "passive"))
      (node (ref "C137") (pin "1") (pinfunction "POS_1") (pintype "passive"))
      (node (ref "C138") (pin "1") (pinfunction "POS_1") (pintype "passive"))
      (node (ref "C139") (pin "1") (pinfunction "POS_1") (pintype "passive"))
      (node (ref "C98") (pin "2") (pinfunction "NEG_2") (pintype "passive"))
      (node (ref "C99") (pin "2") (pinfunction "NEG_2") (pintype "passive"))
      (node (ref "D5") (pin "2") (pinfunction "2_2") (pintype "passive"))
      (node (ref "D6") (pin "2") (pinfunction "2_2") (pintype "passive"))
      (node (ref "D7") (pin "1") (pinfunction "1_1") (pintype "passive"))
      (node (ref "D8") (pin "1") (pinfunction "1_1") (pintype "passive"))
      (node (ref "Dz2") (pin "1") (pinfunction "K_1") (pintype "passive"))
      (node (ref "Dz4") (pin "1") (pinfunction "K_1") (pintype "passive"))
      (node (ref "J11") (pin "SH1") (pinfunction "2_SH1") (pintype "passive"))
      (node (ref "J11") (pin "SH2") (pinfunction "2_SH2") (pintype "passive"))
      (node (ref "J11") (pin "SH3") (pinfunction "2_SH3") (pintype "passive"))
      (node (ref "J11") (pin "SH4") (pinfunction "2_SH4") (pintype "passive"))
      (node (ref "J12") (pin "SH1") (pinfunction "2_SH1") (pintype "passive"))
      (node (ref "J12") (pin "SH2") (pinfunction "2_SH2") (pintype "passive"))
      (node (ref "J12") (pin "SH3") (pinfunction "2_SH3") (pintype "passive"))
      (node (ref "J12") (pin "SH4") (pinfunction "2_SH4") (pintype "passive"))
      (node (ref "J14") (pin "SH1") (pinfunction "2_SH1") (pintype "passive"))
      (node (ref "J14") (pin "SH2") (pinfunction "2_SH2") (pintype "passive"))
      (node (ref "J14") (pin "SH3") (pinfunction "2_SH3") (pintype "passive"))
      (node (ref "J14") (pin "SH4") (pinfunction "2_SH4") (pintype "passive"))
      (node (ref "J15") (pin "SH1") (pinfunction "2_SH1") (pintype "passive"))
      (node (ref "J15") (pin "SH2") (pinfunction "2_SH2") (pintype "passive"))
      (node (ref "J15") (pin "SH3") (pinfunction "2_SH3") (pintype "passive"))
      (node (ref "J15") (pin "SH4") (pinfunction "2_SH4") (pintype "passive"))
      (node (ref "J16") (pin "SH1") (pinfunction "2_SH1") (pintype "passive"))
      (node (ref "J16") (pin "SH2") (pinfunction "2_SH2") (pintype "passive"))
      (node (ref "J16") (pin "SH3") (pinfunction "2_SH3") (pintype "passive"))
      (node (ref "J16") (pin "SH4") (pinfunction "2_SH4") (pintype "passive"))
      (node (ref "J17") (pin "SH1") (pinfunction "2_SH1") (pintype "passive"))
      (node (ref "J17") (pin "SH2") (pinfunction "2_SH2") (pintype "passive"))
      (node (ref "J17") (pin "SH3") (pinfunction "2_SH3") (pintype "passive"))
      (node (ref "J17") (pin "SH4") (pinfunction "2_SH4") (pintype "passive"))
      (node (ref "J18") (pin "SH1") (pinfunction "2_SH1") (pintype "passive"))
      (node (ref "J18") (pin "SH2") (pinfunction "2_SH2") (pintype "passive"))
      (node (ref "J18") (pin "SH3") (pinfunction "2_SH3") (pintype "passive"))
      (node (ref "J18") (pin "SH4") (pinfunction "2_SH4") (pintype "passive"))
      (node (ref "J19") (pin "SH1") (pinfunction "2_SH1") (pintype "passive"))
      (node (ref "J19") (pin "SH2") (pinfunction "2_SH2") (pintype "passive"))
      (node (ref "J19") (pin "SH3") (pinfunction "2_SH3") (pintype "passive"))
      (node (ref "J19") (pin "SH4") (pinfunction "2_SH4") (pintype "passive"))
      (node (ref "LED4") (pin "K") (pinfunction "k_K") (pintype "passive"))
      (node (ref "R13") (pin "1") (pinfunction "1_1") (pintype "passive"))
      (node (ref "R17") (pin "1") (pinfunction "1_1") (pintype "passive"))
      (node (ref "R18") (pin "1") (pinfunction "1_1") (pintype "passive"))
      (node (ref "R9") (pin "1") (pinfunction "1_1") (pintype "passive"))
      (node (ref "Rel1") (pin "2") (pinfunction "2_2") (pintype "passive"))
      (node (ref "Rel2") (pin "2") (pinfunction "2_2") (pintype "passive"))
      (node (ref "U14") (pin "3") (pinfunction "+IN_3") (pintype "passive"))
    )
    (net (code "13") (name "Net-(C131-Pad2)") (class "Default")
      (node (ref "C131") (pin "2") (pinfunction "2_2") (pintype "passive"))
      (node (ref "R11") (pin "1") (pinfunction "1_1") (pintype "passive"))
      (node (ref "R12") (pin "1") (pinfunction "1_1") (pintype "passive"))
      (node (ref "R13") (pin "2") (pinfunction "2_2") (pintype "passive"))
    )
    (net (code "14") (name "Net-(D3-Pad2)") (class "Default")
      (node (ref "D3") (pin "2") (pinfunction "2_2") (pintype "passive"))
      (node (ref "D5") (pin "1") (pinfunction "1_1") (pintype "passive"))
      (node (ref "J9") (pin "1") (pinfunction "1_1") (pintype "passive"))
    )
    (net (code "15") (name "Net-(D4-Pad2)") (class "Default")
      (node (ref "D4") (pin "2") (pinfunction "2_2") (pintype "passive"))
      (node (ref "D6") (pin "1") (pinfunction "1_1") (pintype "passive"))
      (node (ref "J9") (pin "S1") (pinfunction "2_S1") (pintype "passive"))
      (node (ref "J9") (pin "S2") (pinfunction "2_S2") (pintype "passive"))
      (node (ref "J9") (pin "S3") (pinfunction "2_S3") (pintype "passive"))
      (node (ref "J9") (pin "S4") (pinfunction "2_S4") (pintype "passive"))
    )
    (net (code "16") (name "Net-(D7-Pad2)") (class "Default")
      (node (ref "D7") (pin "2") (pinfunction "2_2") (pintype "passive"))
      (node (ref "D9") (pin "1") (pinfunction "1_1") (pintype "passive"))
      (node (ref "J10") (pin "1") (pinfunction "1_1") (pintype "passive"))
    )
    (net (code "17") (name "Net-(D10-Pad1)") (class "Default")
      (node (ref "D10") (pin "1") (pinfunction "1_1") (pintype "passive"))
      (node (ref "D8") (pin "2") (pinfunction "2_2") (pintype "passive"))
      (node (ref "J10") (pin "S1") (pinfunction "2_S1") (pintype "passive"))
      (node (ref "J10") (pin "S2") (pinfunction "2_S2") (pintype "passive"))
      (node (ref "J10") (pin "S3") (pinfunction "2_S3") (pintype "passive"))
      (node (ref "J10") (pin "S4") (pinfunction "2_S4") (pintype "passive"))
    )
    (net (code "18") (name "Net-(Dz1-A)") (class "Default")
      (node (ref "Dz1") (pin "2") (pinfunction "A_2") (pintype "passive"))
      (node (ref "Dz2") (pin "2") (pinfunction "A_2") (pintype "passive"))
    )
    (net (code "19") (name "Net-(Dz3-A)") (class "Default")
      (node (ref "Dz3") (pin "2") (pinfunction "A_2") (pintype "passive"))
      (node (ref "Dz4") (pin "2") (pinfunction "A_2") (pintype "passive"))
    )
    (net (code "20") (name "Net-(LED4-PadA)") (class "Default")
      (node (ref "LED4") (pin "A") (pinfunction "A_A") (pintype "passive"))
      (node (ref "R16") (pin "1") (pinfunction "1_1") (pintype "passive"))
    )
    (net (code "21") (name "Net-(R14-Pad1)") (class "Default")
      (node (ref "R14") (pin "1") (pinfunction "1_1") (pintype "passive"))
      (node (ref "Rel1") (pin "1") (pinfunction "1_1") (pintype "passive"))
    )
    (net (code "22") (name "Net-(R15-Pad1)") (class "Default")
      (node (ref "R15") (pin "1") (pinfunction "1_1") (pintype "passive"))
      (node (ref "Rel2") (pin "1") (pinfunction "1_1") (pintype "passive"))
    )
    (net (code "23") (name "Net-(U14A--IN)") (class "Default")
      (node (ref "R10") (pin "1") (pinfunction "1_1") (pintype "passive"))
      (node (ref "R12") (pin "2") (pinfunction "2_2") (pintype "passive"))
      (node (ref "U14") (pin "2") (pinfunction "-IN_2") (pintype "passive"))
    )
    (net (code "24") (name "Net-(U14B-+IN)") (class "Default")
      (node (ref "C114") (pin "2") (pinfunction "2_2") (pintype "passive"))
      (node (ref "R8") (pin "1") (pinfunction "1_1") (pintype "passive"))
      (node (ref "R9") (pin "2") (pinfunction "2_2") (pintype "passive"))
      (node (ref "U14") (pin "5") (pinfunction "+IN_5") (pintype "passive"))
    )
    (net (code "25") (name "unconnected-(Rel1-Pad3)") (class "Default")
      (node (ref "Rel1") (pin "3") (pinfunction "3_3") (pintype "passive+no_connect"))
    )
    (net (code "26") (name "unconnected-(Rel1-Pad4)") (class "Default")
      (node (ref "Rel1") (pin "4") (pinfunction "4_4") (pintype "passive+no_connect"))
    )
    (net (code "27") (name "unconnected-(Rel2-Pad3)") (class "Default")
      (node (ref "Rel2") (pin "3") (pinfunction "3_3") (pintype "passive+no_connect"))
    )
    (net (code "28") (name "unconnected-(Rel2-Pad4)") (class "Default")
      (node (ref "Rel2") (pin "4") (pinfunction "4_4") (pintype "passive+no_connect"))
    )
  )
)
